# Controller_Board_-_Connectors.net
KiCad netlist of a schematic drawn in Altium Designer
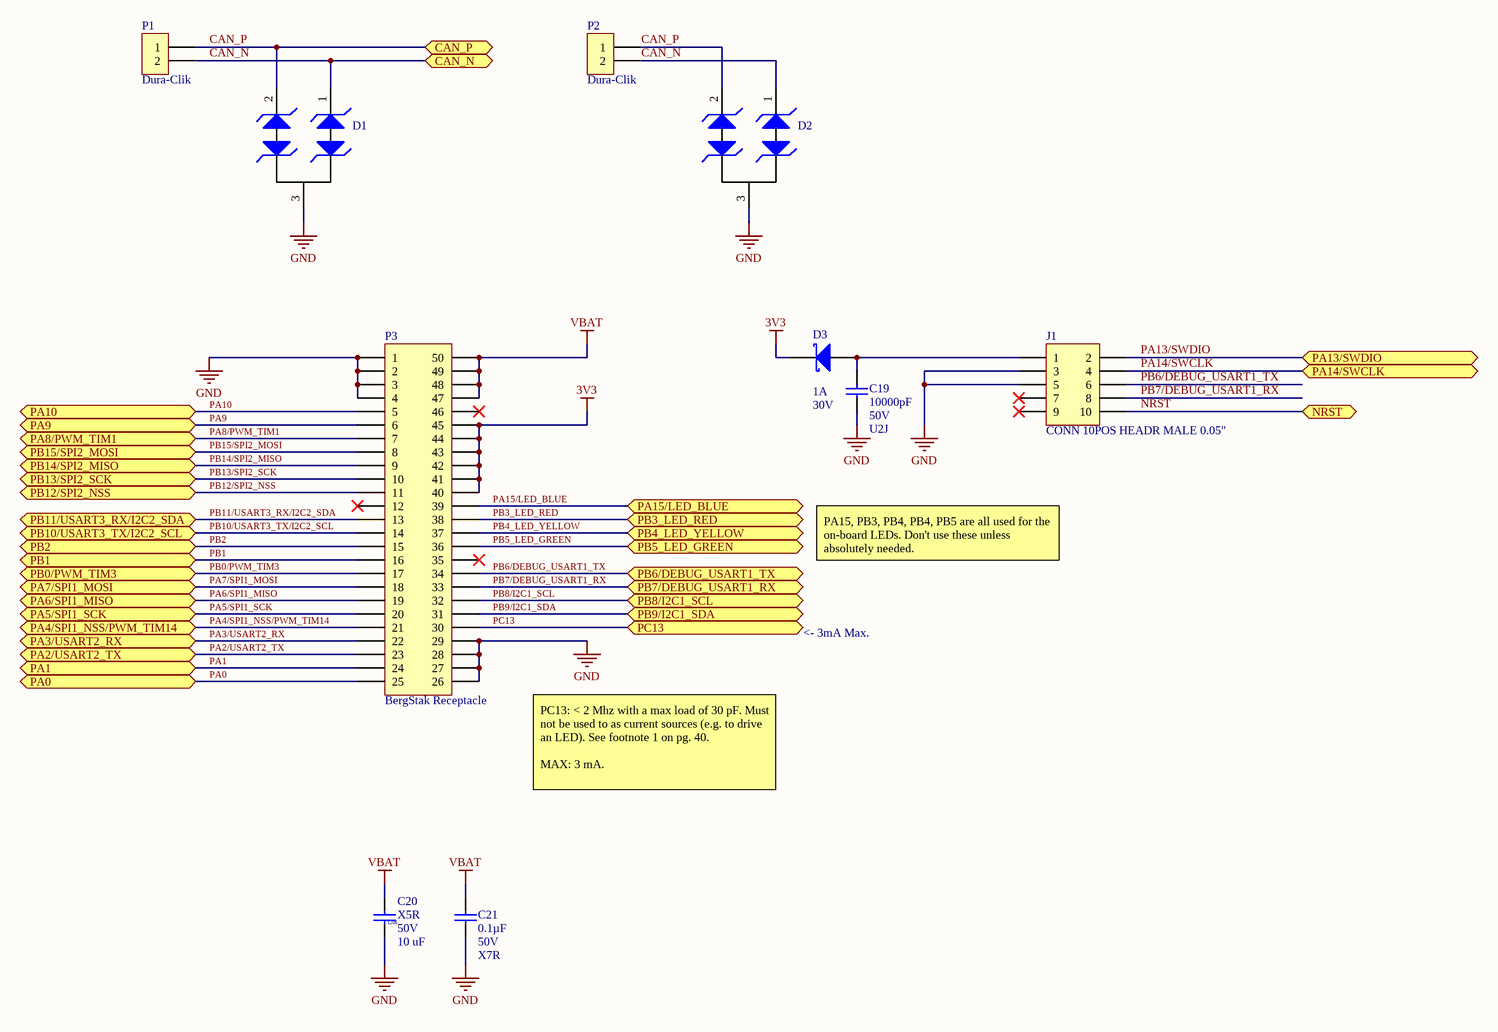
[diagram p0: Controller Board - Connectors.SchDoc]

(export (version "E")
  (design (tool "Eeschema 10.0.6"))
  (components
    (comp (ref "C19")
      (value "CAP CER 10nF 50V 5% X7R 0603")
      (footprint "CAP, 0603")
      (description "10000pF ±5% 50V Ceramic Capacitor U2J 0603 (1608 Metric)")
      (fields
        (field (name "TOLERANCE") "±5%")
        (field (name "CAPACITANCE") "10000pF")
        (field (name "VOLTAGE") "50V")
        (field (name "TEMPERATURE COEFFICIENT") "U2J")
      )
      (libsource (lib "Schematic Diagrams") (part "CAP CER 10nF 50V 5% X7R 0603"))
    )
    (comp (ref "C20")
      (value "CAP CER 10uF 50V 20% X5R 1206")
      (footprint "CAP, 1206")
      (description "10µF ±20% 50V Ceramic Capacitor X5R 1206 (3216 Metric)")
      (fields
        (field (name "MANUFACTURER") "Murata")
        (field (name "TOLERANCE") "20%")
        (field (name "RATING") "X5R")
        (field (name "VOLTAGE RATING") "50V")
        (field (name "CAPACITANCE") "10 uF")
      )
      (libsource (lib "Schematic Diagrams") (part "CAP CER 10uF 50V 20% X5R 1206"))
    )
    (comp (ref "C21")
      (value "CAP CER 0.1UF 50V 10% X7R 0603")
      (footprint "CAP, 0603")
      (description "0.10µF ±10% 50V Ceramic Capacitor X7R 0603 (1608 Metric)")
      (fields
        (field (name "TOLERANCE") "±10%")
        (field (name "CAPACITANCE") "0.1µF")
        (field (name "VOLTAGE") "50V")
        (field (name "TEMPERATURE COEFFICIENT") "X7R")
      )
      (libsource (lib "Schematic Diagrams") (part "CAP CER 0.1UF 50V 10% X7R 0603"))
    )
    (comp (ref "D1")
      (value "DIODE TVS 24VWM 70VC SOT23")
      (footprint "MOSFET P-CH 30V 3.8A SOT-23")
      (description "TVS DIODE 24VWM 70VC SOT23")
      (libsource (lib "Schematic Diagrams") (part "DIODE TVS 24VWM 70VC SOT23"))
    )
    (comp (ref "D2")
      (value "DIODE TVS 24VWM 70VC SOT23")
      (footprint "MOSFET P-CH 30V 3.8A SOT-23")
      (description "TVS DIODE 24VWM 70VC SOT23")
      (libsource (lib "Schematic Diagrams") (part "DIODE TVS 24VWM 70VC SOT23"))
    )
    (comp (ref "D3")
      (value "DIODE SCHOTTKY 30V 1A POWERDI123")
      (footprint "DIODE SCHOTTKY 30V 1A POWERDI123")
      (description "Diode Schottky 30V 1A Surface Mount PowerDI™ 123")
      (fields
        (field (name "MANUFACTURER") "Diodes Incorporated")
        (field (name "MANUFACTURER PART NUMBER") "DFLS130L-7")
        (field (name "CURRENT - AVERAGE RECTIFIED (IO)") "1A")
        (field (name "VOLTAGE - DC REVERSE (VR) (MAX)") "30V")
      )
      (libsource (lib "altium-import") (part "root_2_DIODE SCHOTTKY 30V 1A POWERDI123_"))
    )
    (comp (ref "J1")
      (value "CONN 10POS HEADR MALE 0.05\"")
      (footprint "CONN, 10POS 0.05\" Debug Header")
      (description "10 Positions Header Connector 0.050\" (1.27mm) Surface Mount Gold")
      (libsource (lib "Schematic Diagrams") (part "CONN 10POS HEADR MALE 0.05{dblquote}"))
    )
    (comp (ref "P1")
      (value "Dura-Clik")
      (footprint "CONN, 2POS Dura-Click Vertical")
      (description "2 Positions Header, Shrouded Connector 0.079\" (2.00mm) Surface Mount, Vertical Tin")
      (fields
        (field (name "MANUFACTURER") "Molex, LLC")
        (field (name "MANUFACTURER PART NUMBER") "5600200220")
      )
      (libsource (lib "Schematic Diagrams") (part "CONN 2POS DURA-CLIK 0.079{dblquote} VERT"))
    )
    (comp (ref "P2")
      (value "Dura-Clik")
      (footprint "CONN, 2POS Dura-Click Vertical")
      (description "2 Positions Header, Shrouded Connector 0.079\" (2.00mm) Surface Mount, Vertical Tin")
      (fields
        (field (name "MANUFACTURER") "Molex, LLC")
        (field (name "MANUFACTURER PART NUMBER") "5600200220")
      )
      (libsource (lib "Schematic Diagrams") (part "CONN 2POS DURA-CLIK 0.079{dblquote} VERT"))
    )
    (comp (ref "P3")
      (value "CONN 50POS Bergstak Receptacle 0.02\"")
      (footprint "CONN, Bergstak 50 Pos Receptacle")
      (description "50 Position Connector Receptacle, Center Strip Contacts Surface Mount Gold")
      (fields (field (name "SERIES") "BergStak Receptacle"))
      (libsource (lib "Schematic Diagrams") (part "CONN 50POS Bergstak Receptacle 0.02{dblquote}"))
    )
  )
  (nets
    (net (code "1") (name "/CAN_N") (class "Default")
      (node (ref "D1") (pin "1") (pinfunction "Cathode1_1") (pintype "passive"))
      (node (ref "D2") (pin "1") (pinfunction "Cathode1_1") (pintype "passive"))
      (node (ref "P1") (pin "2") (pinfunction "2_2") (pintype "passive"))
      (node (ref "P2") (pin "2") (pinfunction "2_2") (pintype "passive"))
    )
    (net (code "2") (name "/CAN_P") (class "Default")
      (node (ref "D1") (pin "2") (pinfunction "Cathode2_2") (pintype "passive"))
      (node (ref "D2") (pin "2") (pinfunction "Cathode2_2") (pintype "passive"))
      (node (ref "P1") (pin "1") (pinfunction "1_1") (pintype "passive"))
      (node (ref "P2") (pin "1") (pinfunction "1_1") (pintype "passive"))
    )
    (net (code "3") (name "/NRST") (class "Default")
      (node (ref "J1") (pin "10") (pinfunction "10_10") (pintype "passive"))
    )
    (net (code "4") (name "/PA0") (class "Default")
      (node (ref "P3") (pin "25") (pinfunction "25_25") (pintype "passive"))
    )
    (net (code "5") (name "/PA1") (class "Default")
      (node (ref "P3") (pin "24") (pinfunction "24_24") (pintype "passive"))
    )
    (net (code "6") (name "/PA2{slash}USART2_TX") (class "Default")
      (node (ref "P3") (pin "23") (pinfunction "23_23") (pintype "passive"))
    )
    (net (code "7") (name "/PA3{slash}USART2_RX") (class "Default")
      (node (ref "P3") (pin "22") (pinfunction "22_22") (pintype "passive"))
    )
    (net (code "8") (name "/PA4{slash}SPI1_NSS{slash}PWM_TIM14") (class "Default")
      (node (ref "P3") (pin "21") (pinfunction "21_21") (pintype "passive"))
    )
    (net (code "9") (name "/PA5{slash}SPI1_SCK") (class "Default")
      (node (ref "P3") (pin "20") (pinfunction "20_20") (pintype "passive"))
    )
    (net (code "10") (name "/PA6{slash}SPI1_MISO") (class "Default")
      (node (ref "P3") (pin "19") (pinfunction "19_19") (pintype "passive"))
    )
    (net (code "11") (name "/PA7{slash}SPI1_MOSI") (class "Default")
      (node (ref "P3") (pin "18") (pinfunction "18_18") (pintype "passive"))
    )
    (net (code "12") (name "/PA8{slash}PWM_TIM1") (class "Default")
      (node (ref "P3") (pin "7") (pinfunction "7_7") (pintype "passive"))
    )
    (net (code "13") (name "/PA9") (class "Default")
      (node (ref "P3") (pin "6") (pinfunction "6_6") (pintype "passive"))
    )
    (net (code "14") (name "/PA10") (class "Default")
      (node (ref "P3") (pin "5") (pinfunction "5_5") (pintype "passive"))
    )
    (net (code "15") (name "/PA13{slash}SWDIO") (class "Default")
      (node (ref "J1") (pin "2") (pinfunction "2_2") (pintype "passive"))
    )
    (net (code "16") (name "/PA14{slash}SWCLK") (class "Default")
      (node (ref "J1") (pin "4") (pinfunction "4_4") (pintype "passive"))
    )
    (net (code "17") (name "/PA15{slash}LED_BLUE") (class "Default")
      (node (ref "P3") (pin "39") (pinfunction "39_39") (pintype "passive"))
    )
    (net (code "18") (name "/PB0{slash}PWM_TIM3") (class "Default")
      (node (ref "P3") (pin "17") (pinfunction "17_17") (pintype "passive"))
    )
    (net (code "19") (name "/PB1") (class "Default")
      (node (ref "P3") (pin "16") (pinfunction "16_16") (pintype "passive"))
    )
    (net (code "20") (name "/PB2") (class "Default")
      (node (ref "P3") (pin "15") (pinfunction "15_15") (pintype "passive"))
    )
    (net (code "21") (name "/PB3_LED_RED") (class "Default")
      (node (ref "P3") (pin "38") (pinfunction "38_38") (pintype "passive"))
    )
    (net (code "22") (name "/PB4_LED_YELLOW") (class "Default")
      (node (ref "P3") (pin "37") (pinfunction "37_37") (pintype "passive"))
    )
    (net (code "23") (name "/PB5_LED_GREEN") (class "Default")
      (node (ref "P3") (pin "36") (pinfunction "36_36") (pintype "passive"))
    )
    (net (code "24") (name "/PB6{slash}DEBUG_USART1_TX") (class "Default")
      (node (ref "J1") (pin "6") (pinfunction "6_6") (pintype "passive"))
      (node (ref "P3") (pin "34") (pinfunction "34_34") (pintype "passive"))
    )
    (net (code "25") (name "/PB7{slash}DEBUG_USART1_RX") (class "Default")
      (node (ref "J1") (pin "8") (pinfunction "8_8") (pintype "passive"))
      (node (ref "P3") (pin "33") (pinfunction "33_33") (pintype "passive"))
    )
    (net (code "26") (name "/PB8{slash}I2C1_SCL") (class "Default")
      (node (ref "P3") (pin "32") (pinfunction "32_32") (pintype "passive"))
    )
    (net (code "27") (name "/PB9{slash}I2C1_SDA") (class "Default")
      (node (ref "P3") (pin "31") (pinfunction "31_31") (pintype "passive"))
    )
    (net (code "28") (name "/PB10{slash}USART3_TX{slash}I2C2_SCL") (class "Default")
      (node (ref "P3") (pin "14") (pinfunction "14_14") (pintype "passive"))
    )
    (net (code "29") (name "/PB11{slash}USART3_RX{slash}I2C2_SDA") (class "Default")
      (node (ref "P3") (pin "13") (pinfunction "13_13") (pintype "passive"))
    )
    (net (code "30") (name "/PB12{slash}SPI2_NSS") (class "Default")
      (node (ref "P3") (pin "11") (pinfunction "11_11") (pintype "passive"))
    )
    (net (code "31") (name "/PB13{slash}SPI2_SCK") (class "Default")
      (node (ref "P3") (pin "10") (pinfunction "10_10") (pintype "passive"))
    )
    (net (code "32") (name "/PB14{slash}SPI2_MISO") (class "Default")
      (node (ref "P3") (pin "9") (pinfunction "9_9") (pintype "passive"))
    )
    (net (code "33") (name "/PB15{slash}SPI2_MOSI") (class "Default")
      (node (ref "P3") (pin "8") (pinfunction "8_8") (pintype "passive"))
    )
    (net (code "34") (name "/PC13") (class "Default")
      (node (ref "P3") (pin "30") (pinfunction "30_30") (pintype "passive"))
    )
    (net (code "35") (name "3V3") (class "Default")
      (node (ref "D3") (pin "2") (pinfunction "K_2") (pintype "passive"))
      (node (ref "P3") (pin "40") (pinfunction "40_40") (pintype "passive"))
      (node (ref "P3") (pin "41") (pinfunction "41_41") (pintype "passive"))
      (node (ref "P3") (pin "42") (pinfunction "42_42") (pintype "passive"))
      (node (ref "P3") (pin "43") (pinfunction "43_43") (pintype "passive"))
      (node (ref "P3") (pin "44") (pinfunction "44_44") (pintype "passive"))
      (node (ref "P3") (pin "45") (pinfunction "45_45") (pintype "passive"))
    )
    (net (code "36") (name "GND") (class "Default")
      (node (ref "C19") (pin "2") (pinfunction "2_2") (pintype "passive"))
      (node (ref "C20") (pin "2") (pinfunction "2_2") (pintype "passive"))
      (node (ref "C21") (pin "2") (pinfunction "2_2") (pintype "passive"))
      (node (ref "D1") (pin "3") (pinfunction "Common_Cathode_3") (pintype "power_in"))
      (node (ref "D2") (pin "3") (pinfunction "Common_Cathode_3") (pintype "power_in"))
      (node (ref "J1") (pin "3") (pinfunction "3_3") (pintype "passive"))
      (node (ref "J1") (pin "5") (pinfunction "5_5") (pintype "passive"))
      (node (ref "P3") (pin "1") (pinfunction "1_1") (pintype "passive"))
      (node (ref "P3") (pin "2") (pinfunction "2_2") (pintype "passive"))
      (node (ref "P3") (pin "26") (pinfunction "26_26") (pintype "passive"))
      (node (ref "P3") (pin "27") (pinfunction "27_27") (pintype "passive"))
      (node (ref "P3") (pin "28") (pinfunction "28_28") (pintype "passive"))
      (node (ref "P3") (pin "29") (pinfunction "29_29") (pintype "passive"))
      (node (ref "P3") (pin "3") (pinfunction "3_3") (pintype "passive"))
      (node (ref "P3") (pin "4") (pinfunction "4_4") (pintype "passive"))
    )
    (net (code "37") (name "Net-(D3-A)") (class "Default")
      (node (ref "C19") (pin "1") (pinfunction "1_1") (pintype "passive"))
      (node (ref "D3") (pin "1") (pinfunction "A_1") (pintype "passive"))
      (node (ref "J1") (pin "1") (pinfunction "1_1") (pintype "passive"))
    )
    (net (code "38") (name "VBAT") (class "Default")
      (node (ref "C20") (pin "1") (pinfunction "1_1") (pintype "passive"))
      (node (ref "C21") (pin "1") (pinfunction "1_1") (pintype "passive"))
      (node (ref "P3") (pin "47") (pinfunction "47_47") (pintype "passive"))
      (node (ref "P3") (pin "48") (pinfunction "48_48") (pintype "passive"))
      (node (ref "P3") (pin "49") (pinfunction "49_49") (pintype "passive"))
      (node (ref "P3") (pin "50") (pinfunction "50_50") (pintype "passive"))
    )
    (net (code "39") (name "unconnected-(J1-Pad7)") (class "Default")
      (node (ref "J1") (pin "7") (pinfunction "7_7") (pintype "passive+no_connect"))
    )
    (net (code "40") (name "unconnected-(J1-Pad9)") (class "Default")
      (node (ref "J1") (pin "9") (pinfunction "9_9") (pintype "passive+no_connect"))
    )
    (net (code "41") (name "unconnected-(P3-Pad12)") (class "Default")
      (node (ref "P3") (pin "12") (pinfunction "12_12") (pintype "passive+no_connect"))
    )
    (net (code "42") (name "unconnected-(P3-Pad35)") (class "Default")
      (node (ref "P3") (pin "35") (pinfunction "35_35") (pintype "passive+no_connect"))
    )
    (net (code "43") (name "unconnected-(P3-Pad46)") (class "Default")
      (node (ref "P3") (pin "46") (pinfunction "46_46") (pintype "passive+no_connect"))
    )
  )
)
